# sheet5_sensors.net
KiCad netlist of a schematic drawn in Altium Designer
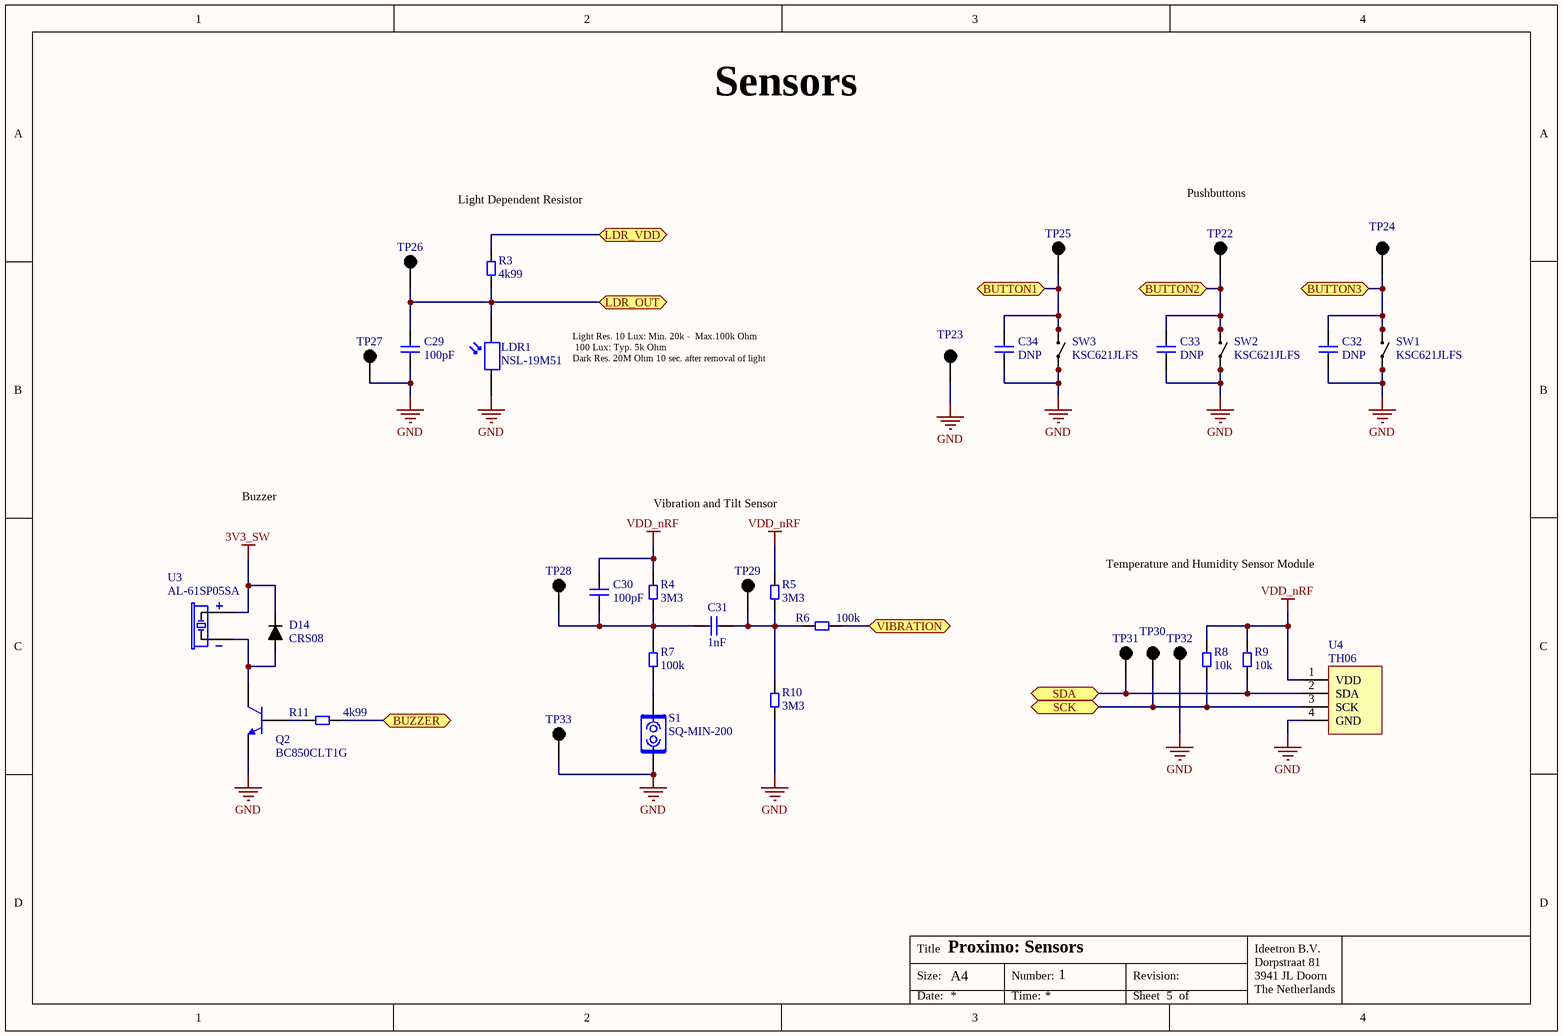
[diagram p0: sheet5_sensors.SchDoc]

(export (version "E")
  (design (tool "Eeschema 10.0.6"))
  (components
    (comp (ref "C29")
      (value "100pF")
      (footprint "CAP0603_GCx18_MURATA")
      (description "Capacitor 100pF 0603 NP0")
      (fields
        (field (name "MANUFACTURER") "Murata")
        (field (name "MANUFACTURER PART NUMBER") "GCM1885C1H101JA16D")
      )
      (libsource (lib "Schlib") (part "CAP_0603_100pF"))
    )
    (comp (ref "C30")
      (value "100pF")
      (footprint "CAP0603_GCx18_MURATA")
      (description "Capacitor 100pF 0603 NP0")
      (fields
        (field (name "MANUFACTURER") "Murata")
        (field (name "MANUFACTURER PART NUMBER") "GCM1885C1H101JA16D")
      )
      (libsource (lib "Schlib") (part "CAP_0603_100pF"))
    )
    (comp (ref "C31")
      (value "1nF")
      (footprint "CAP0402_GCx18_Murata")
      (description "Capacitor 1nF 0402")
      (fields
        (field (name "MANUFACTURER") "Murata")
        (field (name "MANUFACTURER PART NUMBER") "GCM188R72A102KA37D")
      )
      (libsource (lib "Schlib") (part "CAP_0402_1nF"))
    )
    (comp (ref "C32")
      (value "~")
      (footprint "CAP0603_GCx18_MURATA")
      (description "Capacitor 100pF 0603 NP0")
      (fields (field (name "REMARK") "DNP"))
      (libsource (lib "Schlib") (part "CAP_0603_100pF"))
    )
    (comp (ref "C33")
      (value "~")
      (footprint "CAP0603_GCx18_MURATA")
      (description "Capacitor 100pF 0603 NP0")
      (fields (field (name "REMARK") "DNP"))
      (libsource (lib "Schlib") (part "CAP_0603_100pF"))
    )
    (comp (ref "C34")
      (value "~")
      (footprint "CAP0603_GCx18_MURATA")
      (description "Capacitor 100pF 0603 NP0")
      (fields (field (name "REMARK") "DNP"))
      (libsource (lib "Schlib") (part "CAP_0603_100pF"))
    )
    (comp (ref "D14")
      (value "CRS08")
      (footprint "SOD-123F")
      (description "CRS08 Schottky Diode")
      (fields (field (name "MANUFACTURER") "Tohsiba"))
      (libsource (lib "Schlib") (part "CRS08 Schottky Diode"))
    )
    (comp (ref "LDR1")
      (value "NSL-19M51")
      (footprint "LDR")
      (description "Light Dependant Resistor Phot")
      (fields (field (name "MANUFACTURER") "Luna Optoelectronics"))
      (libsource (lib "Schlib") (part "LDR"))
    )
    (comp (ref "Q2")
      (value "BC850CLT1G")
      (footprint "SOT23")
      (description "NPN general purpose transistor")
      (fields
        (field (name "MANUFACTURER") "On Semiconductor")
        (field (name "MANUFACTURER PART NUMBER") "NSVBC850CLT1G")
      )
      (libsource (lib "Schlib") (part "BC850C"))
    )
    (comp (ref "R3")
      (value "4k99")
      (footprint "RES0603VISHAY")
      (description "SMD Resistor 4k99 0603")
      (fields
        (field (name "MANUFACTURER") "Vishay")
        (field (name "MANUFACTURER PART NUMBER") "CRCW06034K99FKTABC")
      )
      (libsource (lib "Schlib") (part "Resistor_4k99"))
    )
    (comp (ref "R4")
      (value "3M3")
      (footprint "RES0603VISHAY")
      (description "SMD Resistor 3M3 0603")
      (fields
        (field (name "MANUFACTURER") "Vishay")
        (field (name "MANUFACTURER PART NUMBER") "CRCW06033M30FKTABC")
      )
      (libsource (lib "Schlib") (part "Resistor_3M3"))
    )
    (comp (ref "R5")
      (value "3M3")
      (footprint "RES0603VISHAY")
      (description "SMD Resistor 3M3 0603")
      (fields
        (field (name "MANUFACTURER") "Vishay")
        (field (name "MANUFACTURER PART NUMBER") "CRCW06033M30FKTABC")
      )
      (libsource (lib "Schlib") (part "Resistor_3M3"))
    )
    (comp (ref "R6")
      (value "100k")
      (footprint "RES0603VISHAY")
      (description "SMD Resistor 100k 0603")
      (fields
        (field (name "MANUFACTURER") "Vishay")
        (field (name "MANUFACTURER PART NUMBER") "CRCW0603100KFKTABC")
      )
      (libsource (lib "Schlib") (part "Resistor_100k"))
    )
    (comp (ref "R7")
      (value "100k")
      (footprint "RES0603VISHAY")
      (description "SMD Resistor 100k 0603")
      (fields
        (field (name "MANUFACTURER") "Vishay")
        (field (name "MANUFACTURER PART NUMBER") "CRCW0603100KFKTABC")
      )
      (libsource (lib "Schlib") (part "Resistor_100k"))
    )
    (comp (ref "R8")
      (value "10k")
      (footprint "RES0603VISHAY")
      (description "SMD Resistor 10k 0603")
      (fields
        (field (name "MANUFACTURER") "Vishay")
        (field (name "MANUFACTURER PART NUMBER") "CRCW060310K0FKTABC")
      )
      (libsource (lib "Schlib") (part "Resistor_10k"))
    )
    (comp (ref "R9")
      (value "10k")
      (footprint "RES0603VISHAY")
      (description "SMD Resistor 10k 0603")
      (fields
        (field (name "MANUFACTURER") "Vishay")
        (field (name "MANUFACTURER PART NUMBER") "CRCW060310K0FKTABC")
      )
      (libsource (lib "Schlib") (part "Resistor_10k"))
    )
    (comp (ref "R10")
      (value "3M3")
      (footprint "RES0603VISHAY")
      (description "SMD Resistor 3M3 0603")
      (fields
        (field (name "MANUFACTURER") "Vishay")
        (field (name "MANUFACTURER PART NUMBER") "CRCW06033M30FKTABC")
      )
      (libsource (lib "Schlib") (part "Resistor_3M3"))
    )
    (comp (ref "R11")
      (value "4k99")
      (footprint "RES0603VISHAY")
      (description "SMD Resistor 4k99 0603")
      (fields
        (field (name "MANUFACTURER") "Vishay")
        (field (name "MANUFACTURER PART NUMBER") "CRCW06034K99FKTABC")
      )
      (libsource (lib "Schlib") (part "Resistor_4k99"))
    )
    (comp (ref "S1")
      (value "SQ-MIN-200")
      (footprint "SQ-SEN-200")
      (description "Nano Power Tilt and Vibration sensor")
      (fields (field (name "MANUFACTURER") "SignalQuest"))
      (libsource (lib "Schlib") (part "SQ-MIN-200"))
    )
    (comp (ref "SW1")
      (value "KSC621JLFS")
      (footprint "KSC621JLFS")
      (description "Tactile switch SMT")
      (fields (field (name "MANUFACTURER") "C & K Components"))
      (libsource (lib "Schlib") (part "KSC621JLFS Tactile switch SMT"))
    )
    (comp (ref "SW2")
      (value "KSC621JLFS")
      (footprint "KSC621JLFS")
      (description "Tactile switch SMT")
      (fields (field (name "MANUFACTURER") "C & K Components"))
      (libsource (lib "Schlib") (part "KSC621JLFS Tactile switch SMT"))
    )
    (comp (ref "SW3")
      (value "KSC621JLFS")
      (footprint "KSC621JLFS")
      (description "Tactile switch SMT")
      (fields (field (name "MANUFACTURER") "C & K Components"))
      (libsource (lib "Schlib") (part "KSC621JLFS Tactile switch SMT"))
    )
    (comp (ref "TP22")
      (value "testpad")
      (footprint "TestPad")
      (description "Signal probe pad")
      (libsource (lib "Schlib") (part "TestPad"))
    )
    (comp (ref "TP23")
      (value "testpad")
      (footprint "TestPad")
      (description "Signal probe pad")
      (libsource (lib "Schlib") (part "TestPad"))
    )
    (comp (ref "TP24")
      (value "testpad")
      (footprint "TestPad")
      (description "Signal probe pad")
      (libsource (lib "Schlib") (part "TestPad"))
    )
    (comp (ref "TP25")
      (value "testpad")
      (footprint "TestPad")
      (description "Signal probe pad")
      (libsource (lib "Schlib") (part "TestPad"))
    )
    (comp (ref "TP26")
      (value "testpad")
      (footprint "TestPad")
      (description "Signal probe pad")
      (libsource (lib "Schlib") (part "TestPad"))
    )
    (comp (ref "TP27")
      (value "testpad")
      (footprint "TestPad")
      (description "Signal probe pad")
      (libsource (lib "Schlib") (part "TestPad"))
    )
    (comp (ref "TP28")
      (value "testpad")
      (footprint "TestPad")
      (description "Signal probe pad")
      (libsource (lib "Schlib") (part "TestPad"))
    )
    (comp (ref "TP29")
      (value "testpad")
      (footprint "TestPad")
      (description "Signal probe pad")
      (libsource (lib "Schlib") (part "TestPad"))
    )
    (comp (ref "TP30")
      (value "testpad")
      (footprint "TestPad")
      (description "Signal probe pad")
      (libsource (lib "Schlib") (part "TestPad"))
    )
    (comp (ref "TP31")
      (value "testpad")
      (footprint "TestPad")
      (description "Signal probe pad")
      (libsource (lib "Schlib") (part "TestPad"))
    )
    (comp (ref "TP32")
      (value "testpad")
      (footprint "TestPad")
      (description "Signal probe pad")
      (libsource (lib "Schlib") (part "TestPad"))
    )
    (comp (ref "TP33")
      (value "testpad")
      (footprint "TestPad")
      (description "Signal probe pad")
      (libsource (lib "Schlib") (part "TestPad"))
    )
    (comp (ref "U3")
      (value "AL-61SP05SA")
      (footprint "Buzzer - AL-61SP05SA")
      (description "Piezo Buzzer")
      (fields (field (name "MANUFACTURER") "EKULIT"))
      (libsource (lib "Schlib") (part "PiezoBuzzer"))
    )
    (comp (ref "U4")
      (value "TH06")
      (footprint "TH06_module")
      (description "I2C Humidity and Temperature Sensor module")
      (fields (field (name "MANUFACTURER") "HopeRF"))
      (libsource (lib "Schlib") (part "TH06"))
    )
  )
  (nets
    (net (code "1") (name "/BUTTON1") (class "Default")
      (node (ref "C34") (pin "2") (pinfunction "2_2") (pintype "passive"))
      (node (ref "SW3") (pin "1") (pinfunction "1_1") (pintype "passive"))
      (node (ref "SW3") (pin "2") (pinfunction "2_2") (pintype "passive"))
      (node (ref "TP25") (pin "1") (pinfunction "1_1") (pintype "passive"))
    )
    (net (code "2") (name "/BUTTON2") (class "Default")
      (node (ref "C33") (pin "2") (pinfunction "2_2") (pintype "passive"))
      (node (ref "SW2") (pin "1") (pinfunction "1_1") (pintype "passive"))
      (node (ref "SW2") (pin "2") (pinfunction "2_2") (pintype "passive"))
      (node (ref "TP22") (pin "1") (pinfunction "1_1") (pintype "passive"))
    )
    (net (code "3") (name "/BUTTON3") (class "Default")
      (node (ref "C32") (pin "2") (pinfunction "2_2") (pintype "passive"))
      (node (ref "SW1") (pin "1") (pinfunction "1_1") (pintype "passive"))
      (node (ref "SW1") (pin "2") (pinfunction "2_2") (pintype "passive"))
      (node (ref "TP24") (pin "1") (pinfunction "1_1") (pintype "passive"))
    )
    (net (code "4") (name "/BUZZER") (class "Default")
      (node (ref "R11") (pin "2") (pinfunction "2_2") (pintype "passive"))
    )
    (net (code "5") (name "/LDR_OUT") (class "Default")
      (node (ref "C29") (pin "2") (pinfunction "2_2") (pintype "passive"))
      (node (ref "LDR1") (pin "2") (pinfunction "2_2") (pintype "passive"))
      (node (ref "R3") (pin "1") (pinfunction "1_1") (pintype "passive"))
      (node (ref "TP26") (pin "1") (pinfunction "1_1") (pintype "passive"))
    )
    (net (code "6") (name "/LDR_VDD") (class "Default")
      (node (ref "R3") (pin "2") (pinfunction "2_2") (pintype "passive"))
    )
    (net (code "7") (name "/SCK") (class "Default")
      (node (ref "R8") (pin "1") (pinfunction "1_1") (pintype "passive"))
      (node (ref "TP30") (pin "1") (pinfunction "1_1") (pintype "passive"))
      (node (ref "U4") (pin "3") (pinfunction "SCK_3") (pintype "passive"))
    )
    (net (code "8") (name "/SDA") (class "Default")
      (node (ref "R9") (pin "1") (pinfunction "1_1") (pintype "passive"))
      (node (ref "TP31") (pin "1") (pinfunction "1_1") (pintype "passive"))
      (node (ref "U4") (pin "2") (pinfunction "SDA_2") (pintype "passive"))
    )
    (net (code "9") (name "/VIBRATION") (class "Default")
      (node (ref "R6") (pin "1") (pinfunction "1_1") (pintype "passive"))
    )
    (net (code "10") (name "3V3_SW") (class "Default")
      (node (ref "D14") (pin "C") (pinfunction "C_C") (pintype "passive"))
      (node (ref "U3") (pin "2") (pinfunction "2_2") (pintype "passive"))
    )
    (net (code "11") (name "GND") (class "Default")
      (node (ref "C29") (pin "1") (pinfunction "1_1") (pintype "passive"))
      (node (ref "C32") (pin "1") (pinfunction "1_1") (pintype "passive"))
      (node (ref "C33") (pin "1") (pinfunction "1_1") (pintype "passive"))
      (node (ref "C34") (pin "1") (pinfunction "1_1") (pintype "passive"))
      (node (ref "LDR1") (pin "1") (pinfunction "1_1") (pintype "passive"))
      (node (ref "Q2") (pin "3") (pinfunction "3_3") (pintype "passive"))
      (node (ref "R10") (pin "1") (pinfunction "1_1") (pintype "passive"))
      (node (ref "S1") (pin "1") (pinfunction "1_1") (pintype "passive"))
      (node (ref "SW1") (pin "3") (pinfunction "3_3") (pintype "passive"))
      (node (ref "SW1") (pin "4") (pinfunction "4_4") (pintype "passive"))
      (node (ref "SW2") (pin "3") (pinfunction "3_3") (pintype "passive"))
      (node (ref "SW2") (pin "4") (pinfunction "4_4") (pintype "passive"))
      (node (ref "SW3") (pin "3") (pinfunction "3_3") (pintype "passive"))
      (node (ref "SW3") (pin "4") (pinfunction "4_4") (pintype "passive"))
      (node (ref "TP23") (pin "1") (pinfunction "1_1") (pintype "passive"))
      (node (ref "TP27") (pin "1") (pinfunction "1_1") (pintype "passive"))
      (node (ref "TP32") (pin "1") (pinfunction "1_1") (pintype "passive"))
      (node (ref "TP33") (pin "1") (pinfunction "1_1") (pintype "passive"))
      (node (ref "U4") (pin "4") (pinfunction "GND_4") (pintype "passive"))
    )
    (net (code "12") (name "Net-(C30-Pad1)") (class "Default")
      (node (ref "C30") (pin "1") (pinfunction "1_1") (pintype "passive"))
      (node (ref "C31") (pin "1") (pinfunction "1_1") (pintype "passive"))
      (node (ref "R4") (pin "1") (pinfunction "1_1") (pintype "passive"))
      (node (ref "R7") (pin "2") (pinfunction "2_2") (pintype "passive"))
      (node (ref "TP28") (pin "1") (pinfunction "1_1") (pintype "passive"))
    )
    (net (code "13") (name "Net-(C31-Pad2)") (class "Default")
      (node (ref "C31") (pin "2") (pinfunction "2_2") (pintype "passive"))
      (node (ref "R10") (pin "2") (pinfunction "2_2") (pintype "passive"))
      (node (ref "R5") (pin "1") (pinfunction "1_1") (pintype "passive"))
      (node (ref "R6") (pin "2") (pinfunction "2_2") (pintype "passive"))
      (node (ref "TP29") (pin "1") (pinfunction "1_1") (pintype "passive"))
    )
    (net (code "14") (name "Net-(D14-PadA)") (class "Default")
      (node (ref "D14") (pin "A") (pinfunction "A_A") (pintype "passive"))
      (node (ref "Q2") (pin "1") (pinfunction "1_1") (pintype "passive"))
      (node (ref "U3") (pin "1") (pinfunction "1_1") (pintype "passive"))
    )
    (net (code "15") (name "Net-(Q2-Pad2)") (class "Default")
      (node (ref "Q2") (pin "2") (pinfunction "2_2") (pintype "passive"))
      (node (ref "R11") (pin "1") (pinfunction "1_1") (pintype "passive"))
    )
    (net (code "16") (name "Net-(R7-Pad1)") (class "Default")
      (node (ref "R7") (pin "1") (pinfunction "1_1") (pintype "passive"))
      (node (ref "S1") (pin "2") (pinfunction "2_2") (pintype "passive"))
    )
    (net (code "17") (name "VDD_nRF") (class "Default")
      (node (ref "C30") (pin "2") (pinfunction "2_2") (pintype "passive"))
      (node (ref "R4") (pin "2") (pinfunction "2_2") (pintype "passive"))
      (node (ref "R5") (pin "2") (pinfunction "2_2") (pintype "passive"))
      (node (ref "R8") (pin "2") (pinfunction "2_2") (pintype "passive"))
      (node (ref "R9") (pin "2") (pinfunction "2_2") (pintype "passive"))
      (node (ref "U4") (pin "1") (pinfunction "VDD_1") (pintype "passive"))
    )
  )
)
